# node_nrf52.net
KiCad netlist of a schematic drawn in Altium Designer
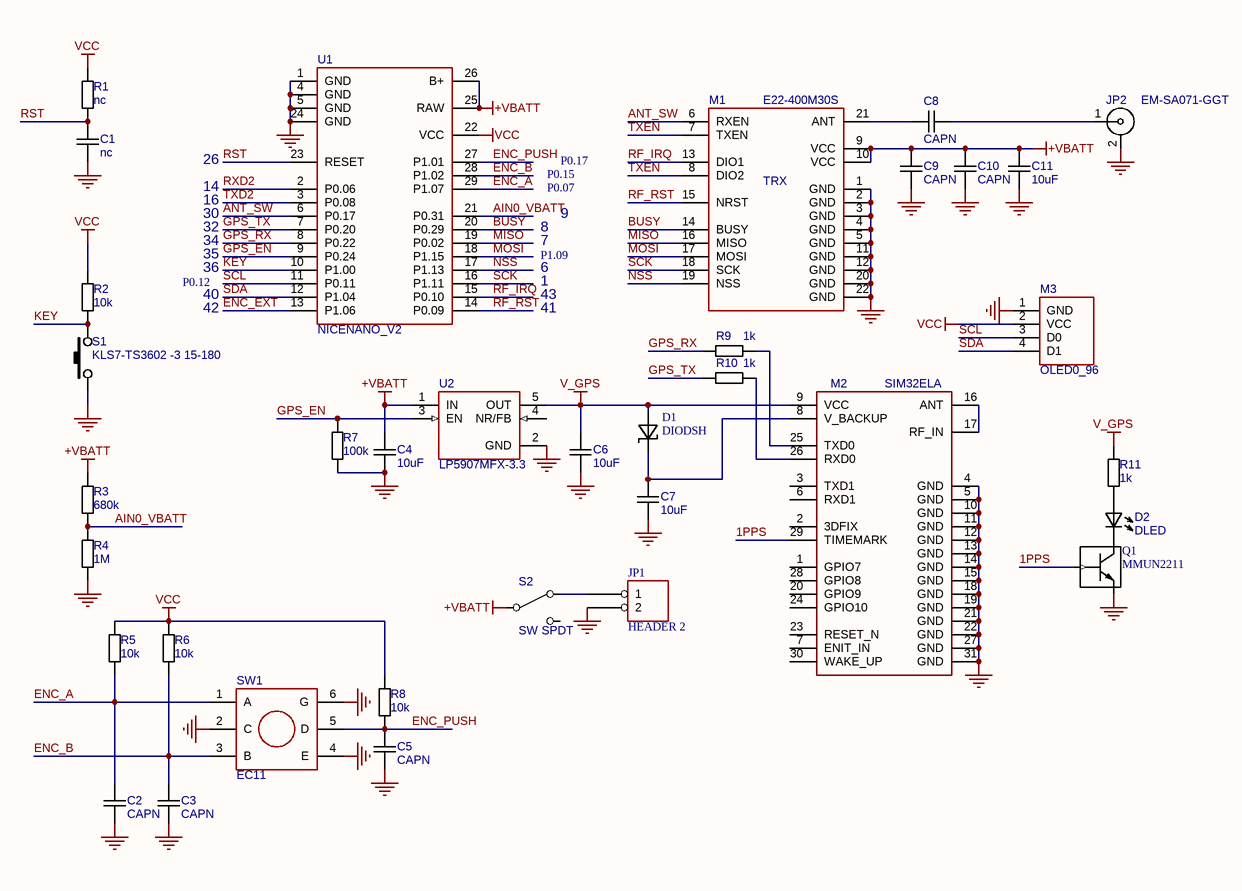
[diagram p0: node_nrf52.SchDoc]

(export (version "E")
  (design (tool "Eeschema 10.0.6"))
  (components
    (comp (ref "C1")
      (value "nc")
      (footprint "C-0603")
      (fields (field (name "VOLTAGE") "50V"))
      (libsource (lib "Passive") (part "CAPN"))
    )
    (comp (ref "C2")
      (value "CAPN")
      (footprint "C-0603")
      (fields (field (name "VOLTAGE") "50V"))
      (libsource (lib "Passive") (part "CAPN"))
    )
    (comp (ref "C3")
      (value "CAPN")
      (footprint "C-0603")
      (fields (field (name "VOLTAGE") "50V"))
      (libsource (lib "Passive") (part "CAPN"))
    )
    (comp (ref "C4")
      (value "10uF")
      (footprint "C-0805")
      (fields (field (name "VOLTAGE") "50V"))
      (libsource (lib "Passive") (part "CAPN"))
    )
    (comp (ref "C5")
      (value "CAPN")
      (footprint "C-0603")
      (fields (field (name "VOLTAGE") "50V"))
      (libsource (lib "Passive") (part "CAPN"))
    )
    (comp (ref "C6")
      (value "10uF")
      (footprint "C-0805")
      (fields (field (name "VOLTAGE") "50V"))
      (libsource (lib "Passive") (part "CAPN"))
    )
    (comp (ref "C7")
      (value "10uF")
      (footprint "C-0805")
      (fields (field (name "VOLTAGE") "50V"))
      (libsource (lib "Passive") (part "CAPN"))
    )
    (comp (ref "C8")
      (value "CAPN")
      (footprint "C-0603")
      (fields (field (name "VOLTAGE") "50V"))
      (libsource (lib "Passive") (part "CAPN"))
    )
    (comp (ref "C9")
      (value "CAPN")
      (footprint "C-0603")
      (fields (field (name "VOLTAGE") "50V"))
      (libsource (lib "Passive") (part "CAPN"))
    )
    (comp (ref "C10")
      (value "CAPN")
      (footprint "C-0603")
      (fields (field (name "VOLTAGE") "50V"))
      (libsource (lib "Passive") (part "CAPN"))
    )
    (comp (ref "C11")
      (value "10uF")
      (footprint "C-0805")
      (fields (field (name "VOLTAGE") "50V"))
      (libsource (lib "Passive") (part "CAPN"))
    )
    (comp (ref "D1") (value "DIODSH") (footprint "SOD80") (libsource (lib "Diodes") (part "DIODSH")))
    (comp (ref "D2") (value "DLED") (footprint "LED_3mm_RED") (libsource (lib "Diodes") (part "DLED")))
    (comp (ref "JP1")
      (value "HEADER 2")
      (footprint "PLS1-2")
      (libsource (lib "Connectors") (part "HEADER 2"))
    )
    (comp (ref "JP2")
      (value "EM-SA071-GGT")
      (footprint "SMA_F_EDGE")
      (description "SMA Female R/A PCB Mount")
      (libsource (lib "Connectors") (part "SMA"))
    )
    (comp (ref "M1")
      (value "E22-400M30S")
      (footprint "PE22(400M30S)")
      (libsource (lib "RFmodules") (part "E22"))
    )
    (comp (ref "M2")
      (value "SIM32ELA")
      (footprint "LGA_SIM32")
      (libsource (lib "RFmodules") (part "SIM32ELA"))
    )
    (comp (ref "M3")
      (value "OLED0_96")
      (footprint "OLED096_I2C")
      (libsource (lib "RFmodules") (part "OLED0_96_I2C"))
    )
    (comp (ref "Q1")
      (value "MMUN2211")
      (footprint "SOT-23")
      (libsource (lib "Transistors") (part "MMUN2211"))
    )
    (comp (ref "R1") (value "nc") (footprint "R-0603") (libsource (lib "") (part "RES_1")))
    (comp (ref "R2") (value "10k") (footprint "R-0603") (libsource (lib "Passive") (part "RES")))
    (comp (ref "R3") (value "680k") (footprint "R-0603") (libsource (lib "") (part "RES_1")))
    (comp (ref "R4") (value "1M") (footprint "R-0603") (libsource (lib "") (part "RES_1")))
    (comp (ref "R5") (value "10k") (footprint "R-0603") (libsource (lib "Passive") (part "RES")))
    (comp (ref "R6") (value "10k") (footprint "R-0603") (libsource (lib "Passive") (part "RES")))
    (comp (ref "R7") (value "100k") (footprint "R-0603") (libsource (lib "") (part "RES_1")))
    (comp (ref "R8") (value "10k") (footprint "R-0603") (libsource (lib "Passive") (part "RES")))
    (comp (ref "R9") (value "1k") (footprint "R-0603") (libsource (lib "") (part "RES_2")))
    (comp (ref "R10") (value "1k") (footprint "R-0603") (libsource (lib "") (part "RES_2")))
    (comp (ref "R11") (value "1k") (footprint "R-0603") (libsource (lib "") (part "RES_1")))
    (comp (ref "S1")
      (value "KLS7-TS3602 -3 15-180")
      (footprint "BUTT_MIN")
      (libsource (lib "Switches") (part "SW-1"))
    )
    (comp (ref "S2")
      (value "SW SPDT")
      (footprint "SK-12D07VG5")
      (libsource (lib "Switches") (part "SW SPDT"))
    )
    (comp (ref "SW1") (value "EC11") (footprint "EC11") (libsource (lib "Switches") (part "EC11")))
    (comp (ref "U1")
      (value "NICENANO_V2")
      (footprint "NICENANO_SMD")
      (libsource (lib "MCUs") (part "NICENANO_V2"))
    )
    (comp (ref "U2")
      (value "LP5907MFX-3.3")
      (footprint "SOT-23-5")
      (description "250mA Low-Dropout Regulator")
      (libsource (lib "ICs") (part "LP5907"))
    )
  )
  (nets
    (net (code "1") (name "+VBATT") (class "Default")
      (node (ref "C10") (pin "1") (pinfunction "1_1") (pintype "passive"))
      (node (ref "C11") (pin "1") (pinfunction "1_1") (pintype "passive"))
      (node (ref "C4") (pin "1") (pinfunction "1_1") (pintype "passive"))
      (node (ref "C9") (pin "1") (pinfunction "1_1") (pintype "passive"))
      (node (ref "M1") (pin "10") (pinfunction "VCC_10") (pintype "passive"))
      (node (ref "M1") (pin "9") (pinfunction "VCC_9") (pintype "passive"))
      (node (ref "R3") (pin "2") (pinfunction "2_2") (pintype "passive"))
      (node (ref "S2") (pin "2") (pinfunction "COMMON_2") (pintype "passive"))
      (node (ref "U1") (pin "25") (pinfunction "RAW_25") (pintype "passive"))
      (node (ref "U1") (pin "26") (pinfunction "B+_26") (pintype "passive"))
      (node (ref "U2") (pin "1") (pinfunction "IN_1") (pintype "power_in"))
    )
    (net (code "2") (name "/1PPS") (class "Default")
      (node (ref "M2") (pin "29") (pinfunction "TIMEMARK_29") (pintype "passive"))
      (node (ref "Q1") (pin "1") (pinfunction "BASE_1") (pintype "input"))
    )
    (net (code "3") (name "/AIN0_VBATT") (class "Default")
      (node (ref "R3") (pin "1") (pinfunction "1_1") (pintype "passive"))
      (node (ref "R4") (pin "2") (pinfunction "2_2") (pintype "passive"))
      (node (ref "U1") (pin "21") (pinfunction "P0.31_21") (pintype "passive"))
    )
    (net (code "4") (name "/ANT_SW") (class "Default")
      (node (ref "M1") (pin "6") (pinfunction "RXEN_6") (pintype "passive"))
      (node (ref "U1") (pin "6") (pinfunction "P0.17_6") (pintype "passive"))
    )
    (net (code "5") (name "/BUSY") (class "Default")
      (node (ref "M1") (pin "14") (pinfunction "BUSY_14") (pintype "passive"))
      (node (ref "U1") (pin "20") (pinfunction "P0.29_20") (pintype "passive"))
    )
    (net (code "6") (name "/ENC_A") (class "Default")
      (node (ref "C2") (pin "1") (pinfunction "1_1") (pintype "passive"))
      (node (ref "R5") (pin "2") (pinfunction "2_2") (pintype "passive"))
      (node (ref "SW1") (pin "1") (pinfunction "A_1") (pintype "passive"))
      (node (ref "U1") (pin "29") (pinfunction "P1.07_29") (pintype "passive"))
    )
    (net (code "7") (name "/ENC_B") (class "Default")
      (node (ref "C3") (pin "1") (pinfunction "1_1") (pintype "passive"))
      (node (ref "R6") (pin "2") (pinfunction "2_2") (pintype "passive"))
      (node (ref "SW1") (pin "3") (pinfunction "B_3") (pintype "passive"))
      (node (ref "U1") (pin "28") (pinfunction "P1.02_28") (pintype "passive"))
    )
    (net (code "8") (name "/ENC_EXT") (class "Default")
      (node (ref "U1") (pin "13") (pinfunction "P1.06_13") (pintype "passive"))
    )
    (net (code "9") (name "/ENC_PUSH") (class "Default")
      (node (ref "C5") (pin "1") (pinfunction "1_1") (pintype "passive"))
      (node (ref "R8") (pin "2") (pinfunction "2_2") (pintype "passive"))
      (node (ref "SW1") (pin "5") (pinfunction "D_5") (pintype "passive"))
      (node (ref "U1") (pin "27") (pinfunction "P1.01_27") (pintype "passive"))
    )
    (net (code "10") (name "/GPS_EN") (class "Default")
      (node (ref "R7") (pin "2") (pinfunction "2_2") (pintype "passive"))
      (node (ref "U1") (pin "9") (pinfunction "P0.24_9") (pintype "passive"))
      (node (ref "U2") (pin "3") (pinfunction "EN_3") (pintype "input"))
    )
    (net (code "11") (name "/GPS_RX") (class "Default")
      (node (ref "R9") (pin "2") (pinfunction "2_2") (pintype "passive"))
      (node (ref "U1") (pin "8") (pinfunction "P0.22_8") (pintype "passive"))
    )
    (net (code "12") (name "/GPS_TX") (class "Default")
      (node (ref "R10") (pin "2") (pinfunction "2_2") (pintype "passive"))
      (node (ref "U1") (pin "7") (pinfunction "P0.20_7") (pintype "passive"))
    )
    (net (code "13") (name "/KEY") (class "Default")
      (node (ref "R2") (pin "2") (pinfunction "2_2") (pintype "passive"))
      (node (ref "S1") (pin "2") (pinfunction "2_2") (pintype "passive"))
      (node (ref "U1") (pin "10") (pinfunction "P1.00_10") (pintype "passive"))
    )
    (net (code "14") (name "/MISO") (class "Default")
      (node (ref "M1") (pin "16") (pinfunction "MISO_16") (pintype "passive"))
      (node (ref "U1") (pin "19") (pinfunction "P0.02_19") (pintype "passive"))
    )
    (net (code "15") (name "/MOSI") (class "Default")
      (node (ref "M1") (pin "17") (pinfunction "MOSI_17") (pintype "passive"))
      (node (ref "U1") (pin "18") (pinfunction "P1.15_18") (pintype "passive"))
    )
    (net (code "16") (name "/NSS") (class "Default")
      (node (ref "M1") (pin "19") (pinfunction "NSS_19") (pintype "passive"))
      (node (ref "U1") (pin "17") (pinfunction "P1.13_17") (pintype "passive"))
    )
    (net (code "17") (name "/RF_IRQ") (class "Default")
      (node (ref "M1") (pin "13") (pinfunction "DIO1_13") (pintype "passive"))
      (node (ref "U1") (pin "15") (pinfunction "P0.10_15") (pintype "passive"))
    )
    (net (code "18") (name "/RF_RST") (class "Default")
      (node (ref "M1") (pin "15") (pinfunction "NRST_15") (pintype "passive"))
      (node (ref "U1") (pin "14") (pinfunction "P0.09_14") (pintype "passive"))
    )
    (net (code "19") (name "/RST") (class "Default")
      (node (ref "C1") (pin "1") (pinfunction "1_1") (pintype "passive"))
      (node (ref "R1") (pin "1") (pinfunction "1_1") (pintype "passive"))
      (node (ref "U1") (pin "23") (pinfunction "RESET_23") (pintype "passive"))
    )
    (net (code "20") (name "/RXD2") (class "Default")
      (node (ref "U1") (pin "2") (pinfunction "P0.06_2") (pintype "passive"))
    )
    (net (code "21") (name "/SCK") (class "Default")
      (node (ref "M1") (pin "18") (pinfunction "SCK_18") (pintype "passive"))
      (node (ref "U1") (pin "16") (pinfunction "P1.11_16") (pintype "passive"))
    )
    (net (code "22") (name "/SCL") (class "Default")
      (node (ref "M3") (pin "3") (pinfunction "D0_3") (pintype "passive"))
      (node (ref "U1") (pin "11") (pinfunction "P0.11_11") (pintype "passive"))
    )
    (net (code "23") (name "/SDA") (class "Default")
      (node (ref "M3") (pin "4") (pinfunction "D1_4") (pintype "passive"))
      (node (ref "U1") (pin "12") (pinfunction "P1.04_12") (pintype "passive"))
    )
    (net (code "24") (name "/TXD2") (class "Default")
      (node (ref "U1") (pin "3") (pinfunction "P0.08_3") (pintype "passive"))
    )
    (net (code "25") (name "/TXEN") (class "Default")
      (node (ref "M1") (pin "7") (pinfunction "TXEN_7") (pintype "passive"))
      (node (ref "M1") (pin "8") (pinfunction "DIO2_8") (pintype "passive"))
    )
    (net (code "26") (name "GND") (class "Default")
      (node (ref "C1") (pin "2") (pinfunction "2_2") (pintype "passive"))
      (node (ref "C10") (pin "2") (pinfunction "2_2") (pintype "passive"))
      (node (ref "C11") (pin "2") (pinfunction "2_2") (pintype "passive"))
      (node (ref "C2") (pin "2") (pinfunction "2_2") (pintype "passive"))
      (node (ref "C3") (pin "2") (pinfunction "2_2") (pintype "passive"))
      (node (ref "C4") (pin "2") (pinfunction "2_2") (pintype "passive"))
      (node (ref "C5") (pin "2") (pinfunction "2_2") (pintype "passive"))
      (node (ref "C6") (pin "2") (pinfunction "2_2") (pintype "passive"))
      (node (ref "C7") (pin "2") (pinfunction "2_2") (pintype "passive"))
      (node (ref "C9") (pin "2") (pinfunction "2_2") (pintype "passive"))
      (node (ref "JP1") (pin "2") (pinfunction "2_2") (pintype "passive"))
      (node (ref "JP2") (pin "2") (pinfunction "2_2") (pintype "passive"))
      (node (ref "M1") (pin "1") (pinfunction "GND_1") (pintype "passive"))
      (node (ref "M1") (pin "11") (pinfunction "GND_11") (pintype "passive"))
      (node (ref "M1") (pin "12") (pinfunction "GND_12") (pintype "passive"))
      (node (ref "M1") (pin "2") (pinfunction "GND_2") (pintype "passive"))
      (node (ref "M1") (pin "20") (pinfunction "GND_20") (pintype "passive"))
      (node (ref "M1") (pin "22") (pinfunction "GND_22") (pintype "passive"))
      (node (ref "M1") (pin "3") (pinfunction "GND_3") (pintype "passive"))
      (node (ref "M1") (pin "4") (pinfunction "GND_4") (pintype "passive"))
      (node (ref "M1") (pin "5") (pinfunction "GND_5") (pintype "passive"))
      (node (ref "M2") (pin "10") (pinfunction "GND_10") (pintype "passive"))
      (node (ref "M2") (pin "11") (pinfunction "GND_11") (pintype "passive"))
      (node (ref "M2") (pin "12") (pinfunction "GND_12") (pintype "passive"))
      (node (ref "M2") (pin "13") (pinfunction "GND_13") (pintype "passive"))
      (node (ref "M2") (pin "14") (pinfunction "GND_14") (pintype "passive"))
      (node (ref "M2") (pin "15") (pinfunction "GND_15") (pintype "passive"))
      (node (ref "M2") (pin "18") (pinfunction "GND_18") (pintype "passive"))
      (node (ref "M2") (pin "19") (pinfunction "GND_19") (pintype "passive"))
      (node (ref "M2") (pin "21") (pinfunction "GND_21") (pintype "passive"))
      (node (ref "M2") (pin "22") (pinfunction "GND_22") (pintype "passive"))
      (node (ref "M2") (pin "27") (pinfunction "GND_27") (pintype "passive"))
      (node (ref "M2") (pin "31") (pinfunction "GND_31") (pintype "passive"))
      (node (ref "M2") (pin "4") (pinfunction "GND_4") (pintype "passive"))
      (node (ref "M2") (pin "5") (pinfunction "GND_5") (pintype "passive"))
      (node (ref "M3") (pin "1") (pinfunction "GND_1") (pintype "passive"))
      (node (ref "Q1") (pin "2") (pinfunction "EMITTER_2") (pintype "passive"))
      (node (ref "R4") (pin "1") (pinfunction "1_1") (pintype "passive"))
      (node (ref "R7") (pin "1") (pinfunction "1_1") (pintype "passive"))
      (node (ref "S1") (pin "1") (pinfunction "1_1") (pintype "passive"))
      (node (ref "SW1") (pin "2") (pinfunction "C_2") (pintype "passive"))
      (node (ref "SW1") (pin "4") (pinfunction "E_4") (pintype "passive"))
      (node (ref "SW1") (pin "6") (pinfunction "G_6") (pintype "passive"))
      (node (ref "U1") (pin "1") (pinfunction "GND_1") (pintype "passive"))
      (node (ref "U1") (pin "24") (pinfunction "GND_24") (pintype "passive"))
      (node (ref "U1") (pin "4") (pinfunction "GND_4") (pintype "passive"))
      (node (ref "U1") (pin "5") (pinfunction "GND_5") (pintype "passive"))
      (node (ref "U2") (pin "2") (pinfunction "GND_2") (pintype "power_in"))
    )
    (net (code "27") (name "Net-(C8-Pad2)") (class "Default")
      (node (ref "C8") (pin "2") (pinfunction "2_2") (pintype "passive"))
      (node (ref "JP2") (pin "1") (pinfunction "1_1") (pintype "passive"))
    )
    (net (code "28") (name "Net-(D2-Pad1)") (class "Default")
      (node (ref "D2") (pin "1") (pinfunction "1_1") (pintype "passive"))
      (node (ref "R11") (pin "1") (pinfunction "1_1") (pintype "passive"))
    )
    (net (code "29") (name "Net-(M1-ANT)") (class "Default")
      (node (ref "C8") (pin "1") (pinfunction "1_1") (pintype "passive"))
      (node (ref "M1") (pin "21") (pinfunction "ANT_21") (pintype "passive"))
    )
    (net (code "30") (name "Net-(M2-ANT)") (class "Default")
      (node (ref "M2") (pin "16") (pinfunction "ANT_16") (pintype "passive"))
      (node (ref "M2") (pin "17") (pinfunction "RF_IN_17") (pintype "passive"))
    )
    (net (code "31") (name "Net-(M2-RXD0)") (class "Default")
      (node (ref "M2") (pin "26") (pinfunction "RXD0_26") (pintype "passive"))
      (node (ref "R10") (pin "1") (pinfunction "1_1") (pintype "passive"))
    )
    (net (code "32") (name "Net-(M2-TXD0)") (class "Default")
      (node (ref "M2") (pin "25") (pinfunction "TXD0_25") (pintype "passive"))
      (node (ref "R9") (pin "1") (pinfunction "1_1") (pintype "passive"))
    )
    (net (code "33") (name "Net-(M2-V_BACKUP)") (class "Default")
      (node (ref "C7") (pin "1") (pinfunction "1_1") (pintype "passive"))
      (node (ref "D1") (pin "2") (pinfunction "2_2") (pintype "passive"))
      (node (ref "M2") (pin "8") (pinfunction "V_BACKUP_8") (pintype "passive"))
    )
    (net (code "34") (name "Net-(Q1-COLLECTOR)") (class "Default")
      (node (ref "D2") (pin "2") (pinfunction "2_2") (pintype "passive"))
      (node (ref "Q1") (pin "3") (pinfunction "COLLECTOR_3") (pintype "passive"))
    )
    (net (code "35") (name "Net-(S2-NC)") (class "Default")
      (node (ref "JP1") (pin "1") (pinfunction "1_1") (pintype "passive"))
      (node (ref "S2") (pin "1") (pinfunction "NC_1") (pintype "passive"))
    )
    (net (code "36") (name "VCC") (class "Default")
      (node (ref "M3") (pin "2") (pinfunction "VCC_2") (pintype "passive"))
      (node (ref "R1") (pin "2") (pinfunction "2_2") (pintype "passive"))
      (node (ref "R2") (pin "1") (pinfunction "1_1") (pintype "passive"))
      (node (ref "R5") (pin "1") (pinfunction "1_1") (pintype "passive"))
      (node (ref "R6") (pin "1") (pinfunction "1_1") (pintype "passive"))
      (node (ref "R8") (pin "1") (pinfunction "1_1") (pintype "passive"))
      (node (ref "U1") (pin "22") (pinfunction "VCC_22") (pintype "passive"))
    )
    (net (code "37") (name "V_GPS") (class "Default")
      (node (ref "C6") (pin "1") (pinfunction "1_1") (pintype "passive"))
      (node (ref "D1") (pin "1") (pinfunction "1_1") (pintype "passive"))
      (node (ref "M2") (pin "9") (pinfunction "VCC_9") (pintype "passive"))
      (node (ref "R11") (pin "2") (pinfunction "2_2") (pintype "passive"))
      (node (ref "U2") (pin "5") (pinfunction "OUT_5") (pintype "power_in"))
    )
    (net (code "38") (name "unconnected-(M2-3DFIX-Pad2)") (class "Default")
      (node (ref "M2") (pin "2") (pinfunction "3DFIX_2") (pintype "passive"))
    )
    (net (code "39") (name "unconnected-(M2-ENIT_IN-Pad7)") (class "Default")
      (node (ref "M2") (pin "7") (pinfunction "ENIT_IN_7") (pintype "passive"))
    )
    (net (code "40") (name "unconnected-(M2-GPIO7-Pad1)") (class "Default")
      (node (ref "M2") (pin "1") (pinfunction "GPIO7_1") (pintype "passive"))
    )
    (net (code "41") (name "unconnected-(M2-GPIO8-Pad28)") (class "Default")
      (node (ref "M2") (pin "28") (pinfunction "GPIO8_28") (pintype "passive"))
    )
    (net (code "42") (name "unconnected-(M2-GPIO9-Pad20)") (class "Default")
      (node (ref "M2") (pin "20") (pinfunction "GPIO9_20") (pintype "passive"))
    )
    (net (code "43") (name "unconnected-(M2-GPIO10-Pad24)") (class "Default")
      (node (ref "M2") (pin "24") (pinfunction "GPIO10_24") (pintype "passive"))
    )
    (net (code "44") (name "unconnected-(M2-RESET_N-Pad23)") (class "Default")
      (node (ref "M2") (pin "23") (pinfunction "RESET_N_23") (pintype "passive"))
    )
    (net (code "45") (name "unconnected-(M2-RXD1-Pad6)") (class "Default")
      (node (ref "M2") (pin "6") (pinfunction "RXD1_6") (pintype "passive"))
    )
    (net (code "46") (name "unconnected-(M2-TXD1-Pad3)") (class "Default")
      (node (ref "M2") (pin "3") (pinfunction "TXD1_3") (pintype "passive"))
    )
    (net (code "47") (name "unconnected-(M2-WAKE_UP-Pad30)") (class "Default")
      (node (ref "M2") (pin "30") (pinfunction "WAKE_UP_30") (pintype "passive"))
    )
    (net (code "48") (name "unconnected-(S2-NO-Pad3)") (class "Default")
      (node (ref "S2") (pin "3") (pinfunction "NO_3") (pintype "passive"))
    )
    (net (code "49") (name "unconnected-(U2-NR{slash}FB-Pad4)") (class "Default")
      (node (ref "U2") (pin "4") (pinfunction "NR/FB_4") (pintype "input"))
    )
  )
)
